# tusb211.net
KiCad netlist of a schematic drawn in EAGLE
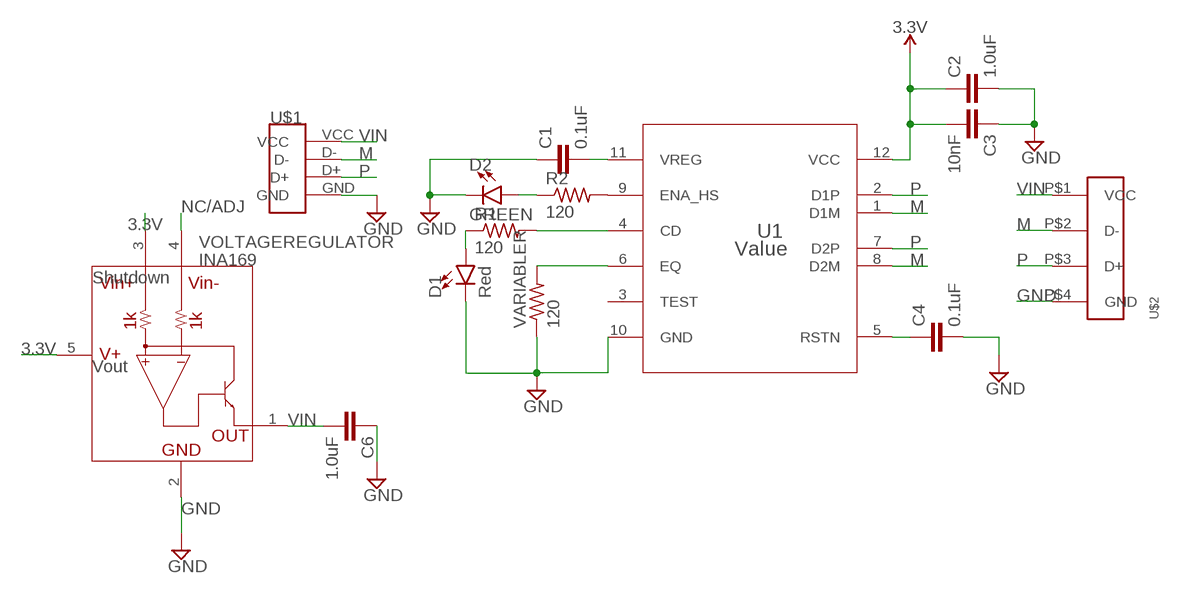
[diagram p0: schematic, sheet 1]

(export (version "E")
  (design (tool "Eeschema 10.0.6"))
  (components
    (comp (ref "C1")
      (value "0.1uF")
      (footprint "eagle-import:0603")
      (libsource (lib "eagle-import") (part "0.1UF-0603-25V-(+80/-20%)"))
    )
    (comp (ref "C2")
      (value "1.0uF")
      (footprint "eagle-import:0603")
      (libsource (lib "eagle-import") (part "1.0UF-0603-16V-10%"))
    )
    (comp (ref "C3")
      (value "10nF")
      (footprint "eagle-import:0603")
      (libsource (lib "eagle-import") (part "10NF-0603-50V-10%"))
    )
    (comp (ref "C4")
      (value "0.1uF")
      (footprint "eagle-import:0603")
      (libsource (lib "eagle-import") (part "0.1UF-0603-25V-(+80/-20%)"))
    )
    (comp (ref "C6")
      (value "1.0uF")
      (footprint "eagle-import:0603")
      (libsource (lib "eagle-import") (part "1.0UF-0603-16V-10%"))
    )
    (comp (ref "D1")
      (value "Red")
      (footprint "eagle-import:LED-0603")
      (libsource (lib "eagle-import") (part "LED-RED0603-SMART"))
    )
    (comp (ref "D2")
      (value "GREEN")
      (footprint "eagle-import:LED-0603")
      (libsource (lib "eagle-import") (part "LED-GREEN0603"))
    )
    (comp (ref "R1")
      (value "120")
      (footprint "eagle-import:R0805")
      (libsource (lib "eagle-import") (part "R-US_R0805"))
    )
    (comp (ref "R2")
      (value "120")
      (footprint "eagle-import:R0805")
      (libsource (lib "eagle-import") (part "R-US_R0805"))
    )
    (comp (ref "U$1")
      (value "TYPEAUSB")
      (footprint "eagle-import:TYPEAUSB")
      (libsource (lib "eagle-import") (part "TYPEAUSB"))
    )
    (comp (ref "U$2")
      (value "USB")
      (footprint "eagle-import:USBSMD")
      (libsource (lib "eagle-import") (part "USB"))
    )
    (comp (ref "U1")
      (value "Value")
      (footprint "eagle-import:RWB0012A")
      (fields (field (name "MANUFACTURER") "Texas Instruments") (field (name "PARTNUMBER") "TUSB211QRWBR"))
      (libsource (lib "eagle-import") (part "TUSB211RWBR"))
    )
    (comp (ref "VARIABLER")
      (value "120")
      (footprint "eagle-import:R0805")
      (libsource (lib "eagle-import") (part "R-US_R0805"))
    )
    (comp (ref "VOLTAGEREGULATOR")
      (value "INA169")
      (footprint "eagle-import:SOT23-5")
      (libsource (lib "eagle-import") (part "INA169"))
    )
  )
  (nets
    (net (code "1") (name "/M") (class "Default")
      (node (ref "U$1") (pin "D-") (pinfunction "D-_D-") (pintype "bidirectional"))
      (node (ref "U$2") (pin "P$2") (pinfunction "D-_P$2") (pintype "bidirectional"))
      (node (ref "U1") (pin "1") (pinfunction "D1M_1") (pintype "bidirectional"))
      (node (ref "U1") (pin "8") (pinfunction "D2M_8") (pintype "bidirectional"))
    )
    (net (code "2") (name "/NC{slash}ADJ") (class "Default")
      (node (ref "VOLTAGEREGULATOR") (pin "4") (pinfunction "VIN-_4") (pintype "bidirectional"))
    )
    (net (code "3") (name "/P") (class "Default")
      (node (ref "U$1") (pin "D+") (pinfunction "D+_D+") (pintype "bidirectional"))
      (node (ref "U$2") (pin "P$3") (pinfunction "D+_P$3") (pintype "bidirectional"))
      (node (ref "U1") (pin "2") (pinfunction "D1P_2") (pintype "bidirectional"))
      (node (ref "U1") (pin "7") (pinfunction "D2P_7") (pintype "bidirectional"))
    )
    (net (code "4") (name "/VIN") (class "Default")
      (node (ref "C6") (pin "2") (pinfunction "2_2") (pintype "passive"))
      (node (ref "U$1") (pin "VCC") (pinfunction "VCC_VCC") (pintype "bidirectional"))
      (node (ref "U$2") (pin "P$1") (pinfunction "VCC_P$1") (pintype "bidirectional"))
      (node (ref "VOLTAGEREGULATOR") (pin "1") (pinfunction "OUT_1") (pintype "bidirectional"))
    )
    (net (code "5") (name "3.3V") (class "Default")
      (node (ref "C2") (pin "1") (pinfunction "1_1") (pintype "passive"))
      (node (ref "C3") (pin "2") (pinfunction "2_2") (pintype "passive"))
      (node (ref "U1") (pin "12") (pinfunction "VCC_12") (pintype "power_in"))
      (node (ref "VOLTAGEREGULATOR") (pin "3") (pinfunction "VIN+_3") (pintype "bidirectional"))
      (node (ref "VOLTAGEREGULATOR") (pin "5") (pinfunction "V+_5") (pintype "bidirectional"))
    )
    (net (code "6") (name "GND") (class "Default")
      (node (ref "C1") (pin "1") (pinfunction "1_1") (pintype "passive"))
      (node (ref "C2") (pin "2") (pinfunction "2_2") (pintype "passive"))
      (node (ref "C3") (pin "1") (pinfunction "1_1") (pintype "passive"))
      (node (ref "C4") (pin "2") (pinfunction "2_2") (pintype "passive"))
      (node (ref "C6") (pin "1") (pinfunction "1_1") (pintype "passive"))
      (node (ref "D1") (pin "C") (pinfunction "C_C") (pintype "passive"))
      (node (ref "D2") (pin "C") (pinfunction "C_C") (pintype "passive"))
      (node (ref "U$1") (pin "GND") (pinfunction "GND_GND") (pintype "bidirectional"))
      (node (ref "U$2") (pin "P$4") (pinfunction "GND_P$4") (pintype "bidirectional"))
      (node (ref "U1") (pin "10") (pinfunction "GND_10") (pintype "power_in"))
      (node (ref "VARIABLER") (pin "1") (pinfunction "1_1") (pintype "passive"))
      (node (ref "VOLTAGEREGULATOR") (pin "2") (pinfunction "GND_2") (pintype "bidirectional"))
    )
    (net (code "7") (name "Net-(D1-PadA)") (class "Default")
      (node (ref "D1") (pin "A") (pinfunction "A_A") (pintype "passive"))
      (node (ref "R1") (pin "1") (pinfunction "1_1") (pintype "passive"))
    )
    (net (code "8") (name "Net-(D2-PadA)") (class "Default")
      (node (ref "D2") (pin "A") (pinfunction "A_A") (pintype "passive"))
      (node (ref "R2") (pin "1") (pinfunction "1_1") (pintype "passive"))
    )
    (net (code "9") (name "Net-(U1-CD)") (class "Default")
      (node (ref "R1") (pin "2") (pinfunction "2_2") (pintype "passive"))
      (node (ref "U1") (pin "4") (pinfunction "CD_4") (pintype "output"))
    )
    (net (code "10") (name "Net-(U1-ENA_HS)") (class "Default")
      (node (ref "R2") (pin "2") (pinfunction "2_2") (pintype "passive"))
      (node (ref "U1") (pin "9") (pinfunction "ENA_HS_9") (pintype "output"))
    )
    (net (code "11") (name "Net-(U1-EQ)") (class "Default")
      (node (ref "U1") (pin "6") (pinfunction "EQ_6") (pintype "input"))
      (node (ref "VARIABLER") (pin "2") (pinfunction "2_2") (pintype "passive"))
    )
    (net (code "12") (name "Net-(U1-RSTN)") (class "Default")
      (node (ref "C4") (pin "1") (pinfunction "1_1") (pintype "passive"))
      (node (ref "U1") (pin "5") (pinfunction "RSTN_5") (pintype "input"))
    )
    (net (code "13") (name "Net-(U1-VREG)") (class "Default")
      (node (ref "C1") (pin "2") (pinfunction "2_2") (pintype "passive"))
      (node (ref "U1") (pin "11") (pinfunction "VREG_11") (pintype "power_in"))
    )
    (net (code "14") (name "unconnected-(U1-TEST-Pad3)") (class "Default")
      (node (ref "U1") (pin "3") (pinfunction "TEST_3") (pintype "passive"))
    )
  )
)
